# MEMORY.net
KiCad netlist of a schematic drawn in Altium Designer
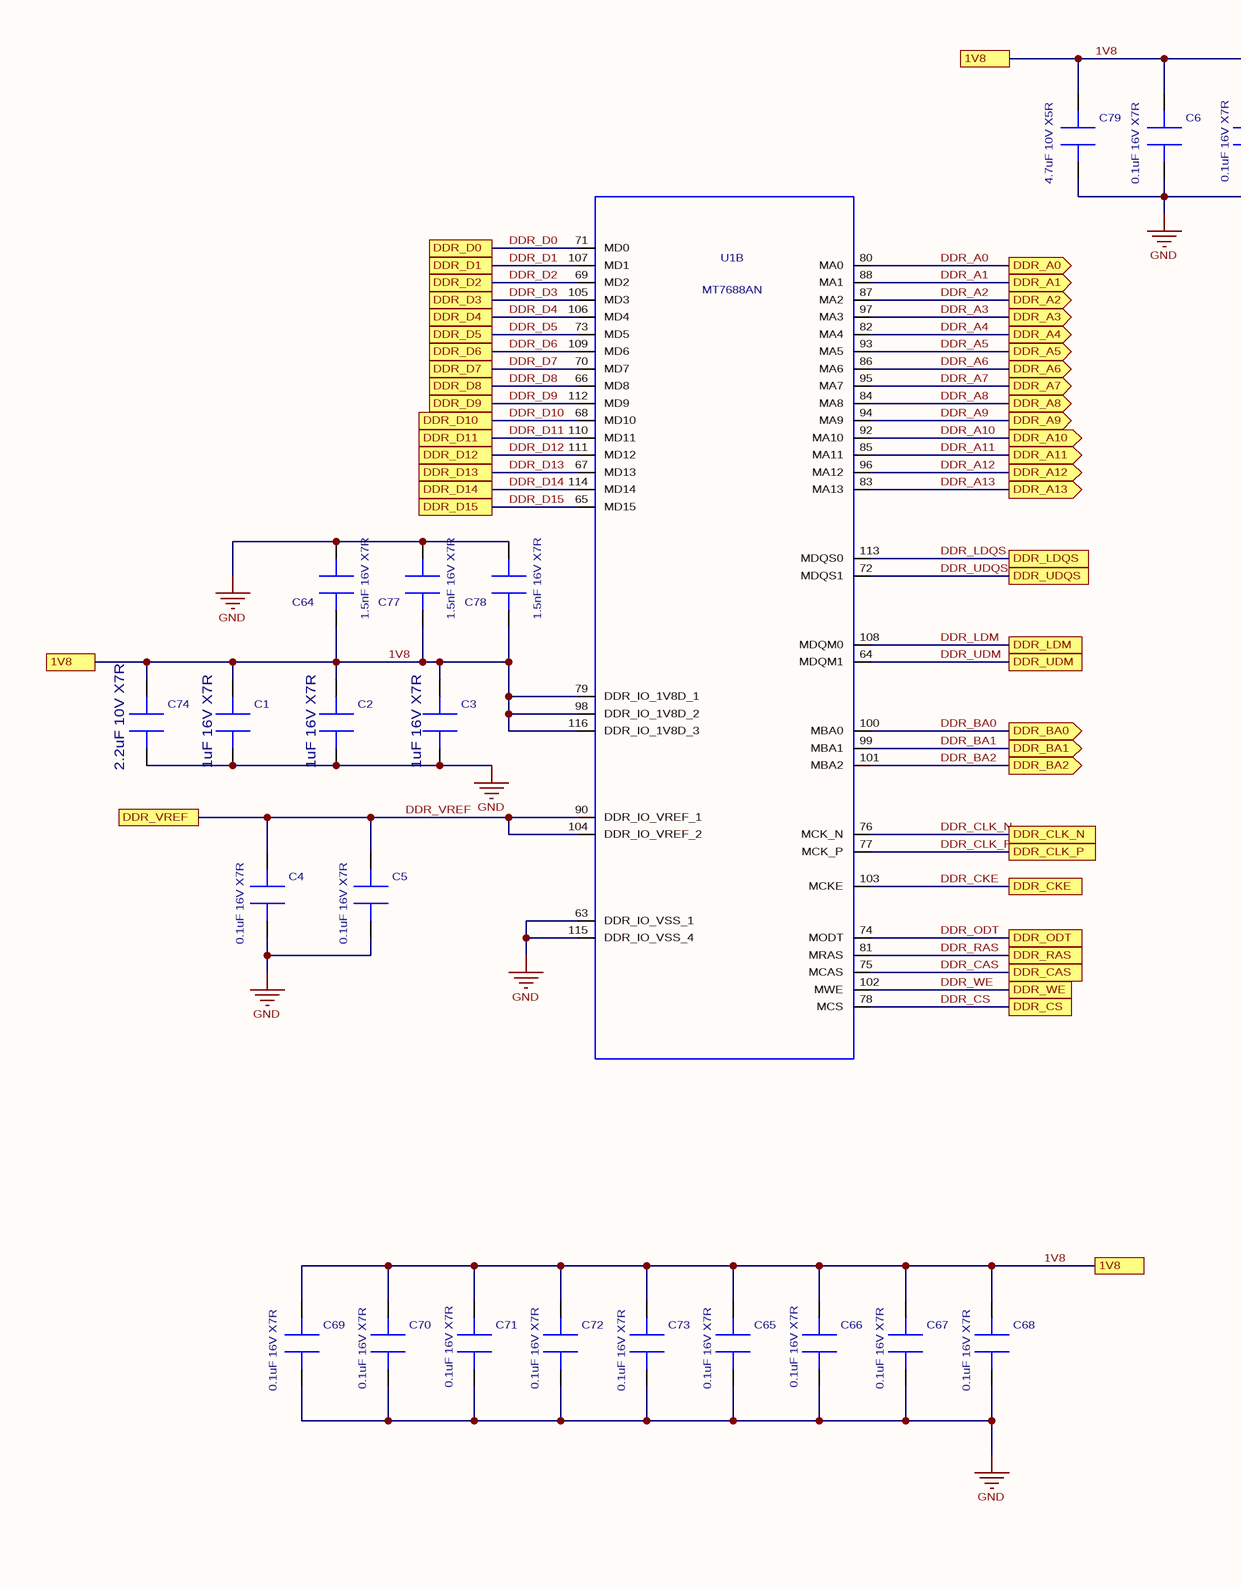
[diagram p0: MEMORY.SchDoc, left]
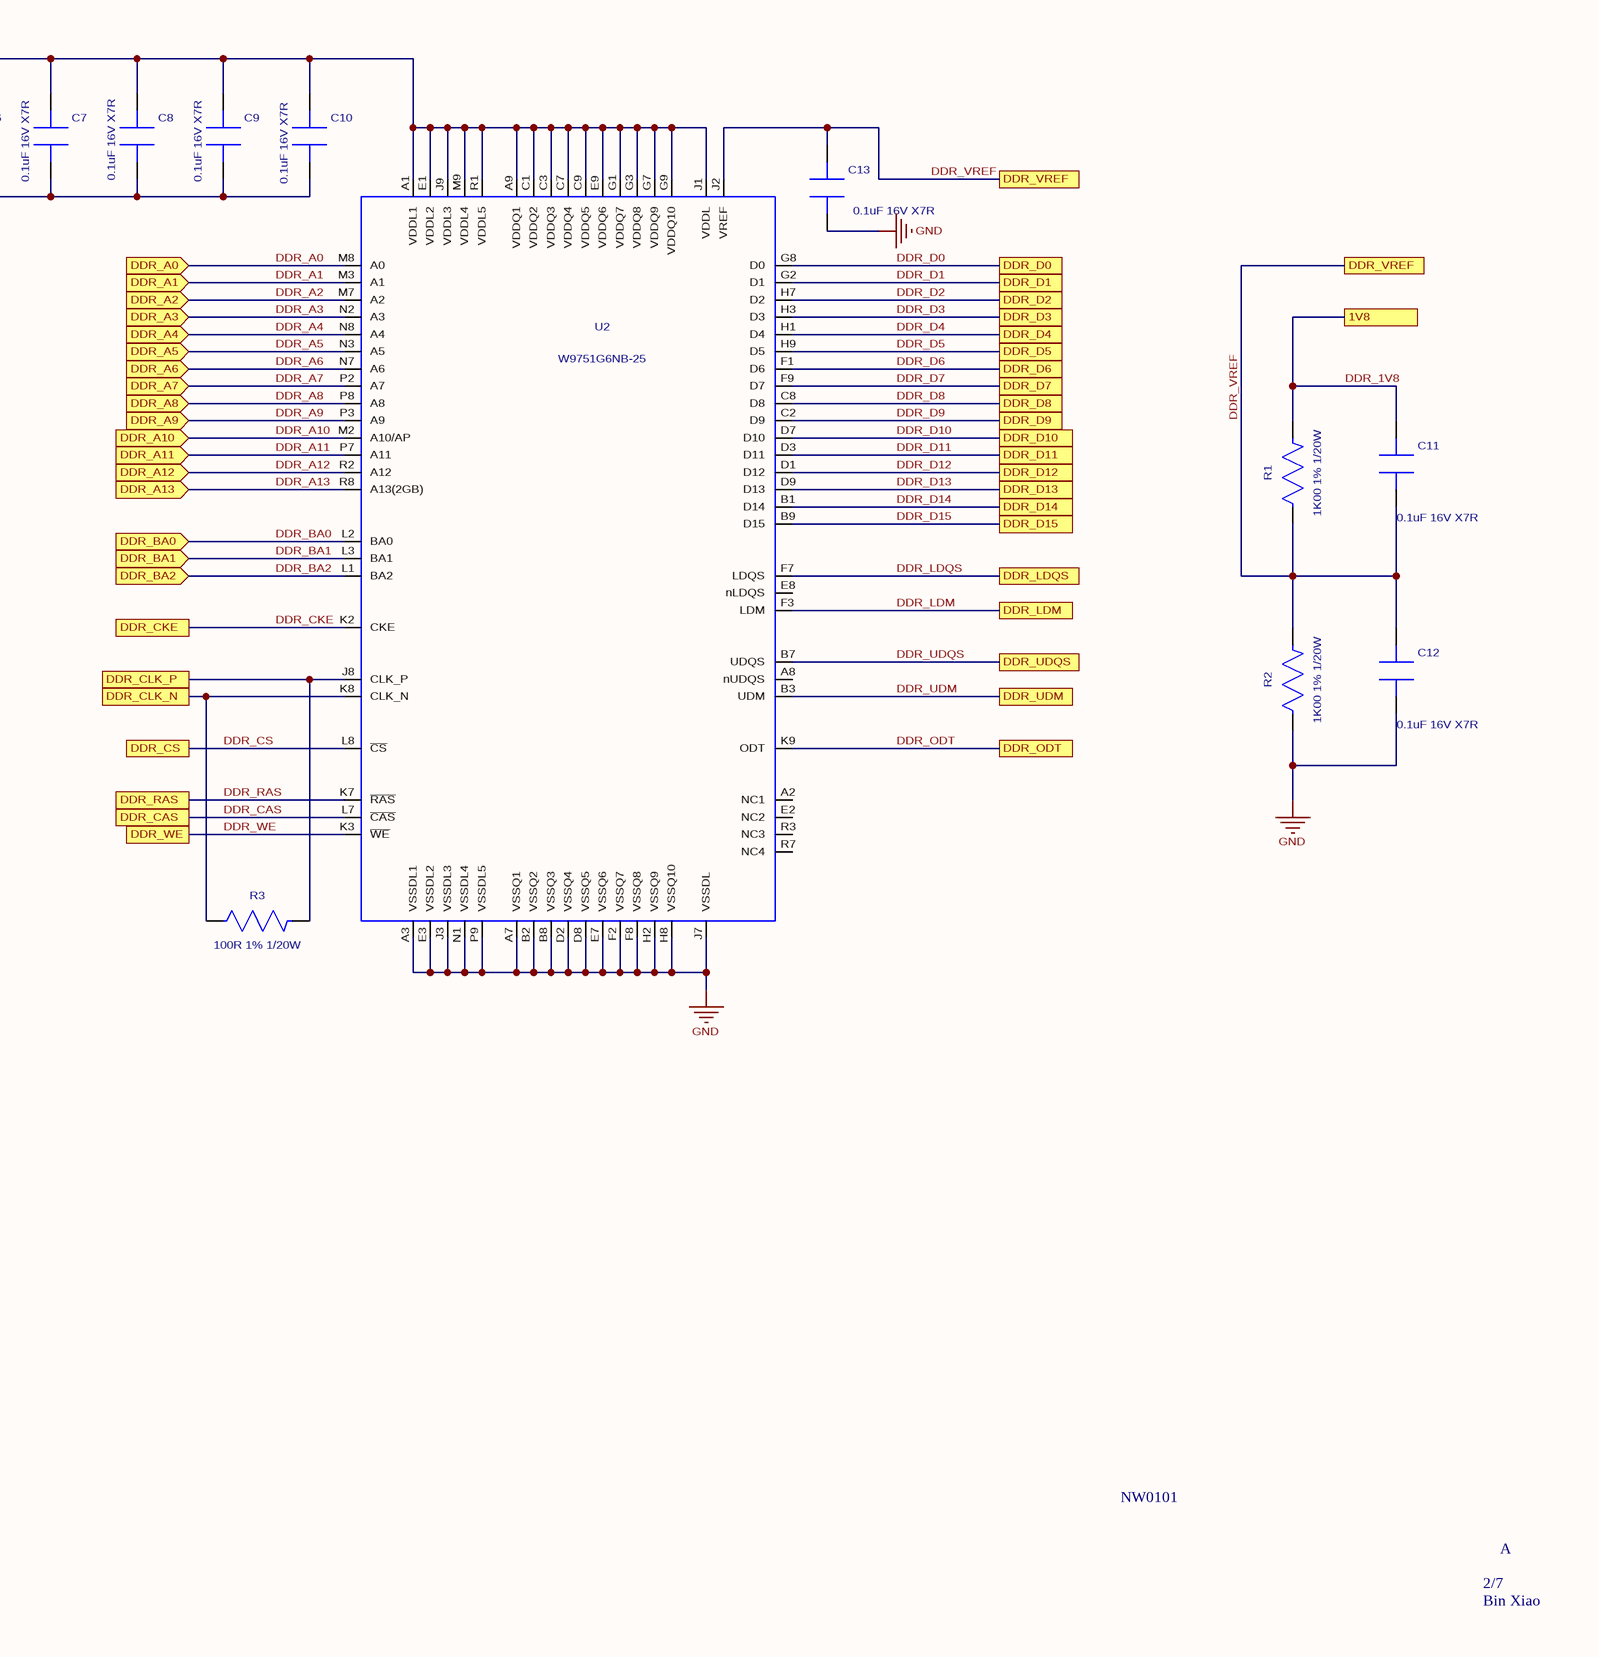
[diagram p1: MEMORY.SchDoc, right]

(export (version "E")
  (design (tool "Eeschema 10.0.6"))
  (components
    (comp (ref "C1")
      (value "1uF 16V X7R")
      (footprint "C0402")
      (description "CAP CER 1UF 6.3V X7R 0402")
      (fields
        (field (name "PART NUMBER") "GRM155R70J105KA12D")
        (field (name "MANUFACTURER") "Murata Electronics")
      )
      (libsource (lib "NetworkModule") (part "CAP0402-105-6.3V-X7R"))
    )
    (comp (ref "C2")
      (value "1uF 16V X7R")
      (footprint "C0402")
      (description "CAP CER 1UF 6.3V X7R 0402")
      (fields
        (field (name "PART NUMBER") "GRM155R70J105KA12D")
        (field (name "MANUFACTURER") "Murata Electronics")
      )
      (libsource (lib "NetworkModule") (part "CAP0402-105-6.3V-X7R"))
    )
    (comp (ref "C3")
      (value "1uF 16V X7R")
      (footprint "C0402")
      (description "CAP CER 1UF 6.3V X7R 0402")
      (fields
        (field (name "PART NUMBER") "GRM155R70J105KA12D")
        (field (name "MANUFACTURER") "Murata Electronics")
      )
      (libsource (lib "NetworkModule") (part "CAP0402-105-6.3V-X7R"))
    )
    (comp (ref "C4")
      (value "0.1uF 16V X7R")
      (footprint "C0201")
      (description "CAP CER 0.1UF 16V X7R 0201")
      (fields
        (field (name "PART NUMBER") "GRM033Z71C104KE14D")
        (field (name "MANUFACTURER") "Murata Electronics")
      )
      (libsource (lib "NetworkModule") (part "CAP0201-104-16V-X7R"))
    )
    (comp (ref "C5")
      (value "0.1uF 16V X7R")
      (footprint "C0201")
      (description "CAP CER 0.1UF 16V X7R 0201")
      (fields
        (field (name "PART NUMBER") "GRM033Z71C104KE14D")
        (field (name "MANUFACTURER") "Murata Electronics")
      )
      (libsource (lib "NetworkModule") (part "CAP0201-104-16V-X7R"))
    )
    (comp (ref "C6")
      (value "0.1uF 16V X7R")
      (footprint "C0201")
      (description "CAP CER 0.1UF 16V X7R 0201")
      (fields
        (field (name "PART NUMBER") "GRM033Z71C104KE14D")
        (field (name "MANUFACTURER") "Murata Electronics")
      )
      (libsource (lib "NetworkModule") (part "CAP0201-104-16V-X7R"))
    )
    (comp (ref "C7")
      (value "0.1uF 16V X7R")
      (footprint "C0201")
      (description "CAP CER 0.1UF 16V X7R 0201")
      (fields
        (field (name "PART NUMBER") "GRM033Z71C104KE14D")
        (field (name "MANUFACTURER") "Murata Electronics")
      )
      (libsource (lib "NetworkModule") (part "CAP0201-104-16V-X7R"))
    )
    (comp (ref "C8")
      (value "0.1uF 16V X7R")
      (footprint "C0201")
      (description "CAP CER 0.1UF 16V X7R 0201")
      (fields
        (field (name "PART NUMBER") "GRM033Z71C104KE14D")
        (field (name "MANUFACTURER") "Murata Electronics")
      )
      (libsource (lib "NetworkModule") (part "CAP0201-104-16V-X7R"))
    )
    (comp (ref "C9")
      (value "0.1uF 16V X7R")
      (footprint "C0201")
      (description "CAP CER 0.1UF 16V X7R 0201")
      (fields
        (field (name "PART NUMBER") "GRM033Z71C104KE14D")
        (field (name "MANUFACTURER") "Murata Electronics")
      )
      (libsource (lib "NetworkModule") (part "CAP0201-104-16V-X7R"))
    )
    (comp (ref "C10")
      (value "0.1uF 16V X7R")
      (footprint "C0201")
      (description "CAP CER 0.1UF 16V X7R 0201")
      (fields
        (field (name "PART NUMBER") "GRM033Z71C104KE14D")
        (field (name "MANUFACTURER") "Murata Electronics")
      )
      (libsource (lib "NetworkModule") (part "CAP0201-104-16V-X7R"))
    )
    (comp (ref "C11")
      (value "0.1uF 16V X7R")
      (footprint "C0201")
      (description "CAP CER 0.1UF 16V X7R 0201")
      (fields
        (field (name "PART NUMBER") "GRM033Z71C104KE14D")
        (field (name "MANUFACTURER") "Murata Electronics")
      )
      (libsource (lib "NetworkModule") (part "CAP0201-104-16V-X7R"))
    )
    (comp (ref "C12")
      (value "0.1uF 16V X7R")
      (footprint "C0201")
      (description "CAP CER 0.1UF 16V X7R 0201")
      (fields
        (field (name "PART NUMBER") "GRM033Z71C104KE14D")
        (field (name "MANUFACTURER") "Murata Electronics")
      )
      (libsource (lib "NetworkModule") (part "CAP0201-104-16V-X7R"))
    )
    (comp (ref "C13")
      (value "0.1uF 16V X7R")
      (footprint "C0201")
      (description "CAP CER 0.1UF 16V X7R 0201")
      (fields
        (field (name "PART NUMBER") "GRM033Z71C104KE14D")
        (field (name "MANUFACTURER") "Murata Electronics")
      )
      (libsource (lib "NetworkModule") (part "CAP0201-104-16V-X7R"))
    )
    (comp (ref "C64")
      (value "1.5nF 16V X7R")
      (footprint "C0201")
      (description "CAP CER 1500PF 16V X7R 0201")
      (fields
        (field (name "PART NUMBER") "CGA1A2X7R1C152K030BA")
        (field (name "MANUFACTURER") "TDK Corporation")
      )
      (libsource (lib "NetworkModule") (part "CAP0201-152-16V-X7R"))
    )
    (comp (ref "C65")
      (value "0.1uF 16V X7R")
      (footprint "C0201")
      (description "CAP CER 0.1UF 16V X7R 0201")
      (fields
        (field (name "PART NUMBER") "GRM033Z71C104KE14D")
        (field (name "MANUFACTURER") "Murata Electronics")
      )
      (libsource (lib "NetworkModule") (part "CAP0201-104-16V-X7R"))
    )
    (comp (ref "C66")
      (value "0.1uF 16V X7R")
      (footprint "C0201")
      (description "CAP CER 0.1UF 16V X7R 0201")
      (fields
        (field (name "PART NUMBER") "GRM033Z71C104KE14D")
        (field (name "MANUFACTURER") "Murata Electronics")
      )
      (libsource (lib "NetworkModule") (part "CAP0201-104-16V-X7R"))
    )
    (comp (ref "C67")
      (value "0.1uF 16V X7R")
      (footprint "C0201")
      (description "CAP CER 0.1UF 16V X7R 0201")
      (fields
        (field (name "PART NUMBER") "GRM033Z71C104KE14D")
        (field (name "MANUFACTURER") "Murata Electronics")
      )
      (libsource (lib "NetworkModule") (part "CAP0201-104-16V-X7R"))
    )
    (comp (ref "C68")
      (value "0.1uF 16V X7R")
      (footprint "C0201")
      (description "CAP CER 0.1UF 16V X7R 0201")
      (fields
        (field (name "PART NUMBER") "GRM033Z71C104KE14D")
        (field (name "MANUFACTURER") "Murata Electronics")
      )
      (libsource (lib "NetworkModule") (part "CAP0201-104-16V-X7R"))
    )
    (comp (ref "C69")
      (value "0.1uF 16V X7R")
      (footprint "C0201")
      (description "CAP CER 0.1UF 16V X7R 0201")
      (fields
        (field (name "PART NUMBER") "GRM033Z71C104KE14D")
        (field (name "MANUFACTURER") "Murata Electronics")
      )
      (libsource (lib "NetworkModule") (part "CAP0201-104-16V-X7R"))
    )
    (comp (ref "C70")
      (value "0.1uF 16V X7R")
      (footprint "C0201")
      (description "CAP CER 0.1UF 16V X7R 0201")
      (fields
        (field (name "PART NUMBER") "GRM033Z71C104KE14D")
        (field (name "MANUFACTURER") "Murata Electronics")
      )
      (libsource (lib "NetworkModule") (part "CAP0201-104-16V-X7R"))
    )
    (comp (ref "C71")
      (value "0.1uF 16V X7R")
      (footprint "C0201")
      (description "CAP CER 0.1UF 16V X7R 0201")
      (fields
        (field (name "PART NUMBER") "GRM033Z71C104KE14D")
        (field (name "MANUFACTURER") "Murata Electronics")
      )
      (libsource (lib "NetworkModule") (part "CAP0201-104-16V-X7R"))
    )
    (comp (ref "C72")
      (value "0.1uF 16V X7R")
      (footprint "C0201")
      (description "CAP CER 0.1UF 16V X7R 0201")
      (fields
        (field (name "PART NUMBER") "GRM033Z71C104KE14D")
        (field (name "MANUFACTURER") "Murata Electronics")
      )
      (libsource (lib "NetworkModule") (part "CAP0201-104-16V-X7R"))
    )
    (comp (ref "C73")
      (value "0.1uF 16V X7R")
      (footprint "C0201")
      (description "CAP CER 0.1UF 16V X7R 0201")
      (fields
        (field (name "PART NUMBER") "GRM033Z71C104KE14D")
        (field (name "MANUFACTURER") "Murata Electronics")
      )
      (libsource (lib "NetworkModule") (part "CAP0201-104-16V-X7R"))
    )
    (comp (ref "C74")
      (value "2.2uF 10V X7R")
      (footprint "C0402")
      (description "CAP CER 2.2UF 10V X7R 0402")
      (fields
        (field (name "PART NUMBER") "GRM155Z71A225KE01D")
        (field (name "MANUFACTURER") "Murata Electronics")
      )
      (libsource (lib "NetworkModule") (part "CAP0402-225-6.3V-X7R"))
    )
    (comp (ref "C77")
      (value "1.5nF 16V X7R")
      (footprint "C0201")
      (description "CAP CER 1500PF 16V X7R 0201")
      (fields
        (field (name "PART NUMBER") "CGA1A2X7R1C152K030BA")
        (field (name "MANUFACTURER") "TDK Corporation")
      )
      (libsource (lib "NetworkModule") (part "CAP0201-152-16V-X7R"))
    )
    (comp (ref "C78")
      (value "1.5nF 16V X7R")
      (footprint "C0201")
      (description "CAP CER 1500PF 16V X7R 0201")
      (fields
        (field (name "PART NUMBER") "CGA1A2X7R1C152K030BA")
        (field (name "MANUFACTURER") "TDK Corporation")
      )
      (libsource (lib "NetworkModule") (part "CAP0201-152-16V-X7R"))
    )
    (comp (ref "C79")
      (value "4.7uF 10V X5R")
      (footprint "C0402")
      (description "CAP CER 4.7UF 10V X5R 0402")
      (fields
        (field (name "PART NUMBER") "CL05A475MP5NRNC")
        (field (name "MANUFACTURER") "Samsung Electro-Mechanics")
      )
      (libsource (lib "NetworkModule") (part "CAP0402-475-10V-X5R"))
    )
    (comp (ref "R1")
      (value "1K00 1% 1/20W")
      (footprint "R0201")
      (description "RES 1K OHM 1% 1/20W 0201")
      (fields
        (field (name "PART NUMBER") "RMCF0201FT1K00")
        (field (name "MANUFACTURER") "Stackpole Electronics Inc")
      )
      (libsource (lib "NetworkModule") (part "RES0201-1K00"))
    )
    (comp (ref "R2")
      (value "1K00 1% 1/20W")
      (footprint "R0201")
      (description "RES 1K OHM 1% 1/20W 0201")
      (fields
        (field (name "PART NUMBER") "RMCF0201FT1K00")
        (field (name "MANUFACTURER") "Stackpole Electronics Inc")
      )
      (libsource (lib "NetworkModule") (part "RES0201-1K00"))
    )
    (comp (ref "R3")
      (value "100R 1% 1/20W")
      (footprint "R0201")
      (description "RES 100 OHM 1% 1/20W 0201")
      (fields (field (name "MANUFACTURER") "Yageo") (field (name "PART NUMBER") "RC0201FR-07100RL"))
      (libsource (lib "NetworkModule") (part "RES0201-100R"))
    )
    (comp (ref "U1")
      (value "MT7688AN")
      (footprint "DR-QFN-128")
      (description "580Mhz 32bits Networking Processor")
      (fields (field (name "MANUFACTURER") "MediaTek Inc"))
      (libsource (lib "*") (part "MT7688AN"))
    )
    (comp (ref "U2")
      (value "W9751G6NB-25")
      (footprint "TWBGA-84_8X12P5_ISI")
      (description "IC DRAM 512MBIT PARALLEL 84VFBGA")
      (fields (field (name "MANUFACTURER") "Winbond Electronics"))
      (libsource (lib "NetworkModule") (part "W9751G6NB-25"))
    )
  )
  (nets
    (net (code "1") (name "/1V8") (class "Default")
      (node (ref "C1") (pin "1") (pinfunction "1_1") (pintype "passive"))
      (node (ref "C10") (pin "1") (pinfunction "1_1") (pintype "passive"))
      (node (ref "C11") (pin "1") (pinfunction "1_1") (pintype "passive"))
      (node (ref "C2") (pin "1") (pinfunction "1_1") (pintype "passive"))
      (node (ref "C3") (pin "1") (pinfunction "1_1") (pintype "passive"))
      (node (ref "C6") (pin "1") (pinfunction "1_1") (pintype "passive"))
      (node (ref "C64") (pin "1") (pinfunction "1_1") (pintype "passive"))
      (node (ref "C65") (pin "1") (pinfunction "1_1") (pintype "passive"))
      (node (ref "C66") (pin "1") (pinfunction "1_1") (pintype "passive"))
      (node (ref "C67") (pin "1") (pinfunction "1_1") (pintype "passive"))
      (node (ref "C68") (pin "1") (pinfunction "1_1") (pintype "passive"))
      (node (ref "C69") (pin "1") (pinfunction "1_1") (pintype "passive"))
      (node (ref "C7") (pin "1") (pinfunction "1_1") (pintype "passive"))
      (node (ref "C70") (pin "1") (pinfunction "1_1") (pintype "passive"))
      (node (ref "C71") (pin "1") (pinfunction "1_1") (pintype "passive"))
      (node (ref "C72") (pin "1") (pinfunction "1_1") (pintype "passive"))
      (node (ref "C73") (pin "1") (pinfunction "1_1") (pintype "passive"))
      (node (ref "C74") (pin "1") (pinfunction "1_1") (pintype "passive"))
      (node (ref "C77") (pin "1") (pinfunction "1_1") (pintype "passive"))
      (node (ref "C78") (pin "1") (pinfunction "1_1") (pintype "passive"))
      (node (ref "C79") (pin "1") (pinfunction "1_1") (pintype "passive"))
      (node (ref "C8") (pin "1") (pinfunction "1_1") (pintype "passive"))
      (node (ref "C9") (pin "1") (pinfunction "1_1") (pintype "passive"))
      (node (ref "R1") (pin "2") (pinfunction "2_2") (pintype "passive"))
      (node (ref "U1") (pin "116") (pinfunction "DDR_IO_1V8D_3_116") (pintype "passive"))
      (node (ref "U1") (pin "79") (pinfunction "DDR_IO_1V8D_1_79") (pintype "passive"))
      (node (ref "U1") (pin "98") (pinfunction "DDR_IO_1V8D_2_98") (pintype "passive"))
      (node (ref "U2") (pin "A1") (pinfunction "VDDL1_A1") (pintype "passive"))
      (node (ref "U2") (pin "A9") (pinfunction "VDDQ1_A9") (pintype "passive"))
      (node (ref "U2") (pin "C1") (pinfunction "VDDQ2_C1") (pintype "passive"))
      (node (ref "U2") (pin "C3") (pinfunction "VDDQ3_C3") (pintype "passive"))
      (node (ref "U2") (pin "C7") (pinfunction "VDDQ4_C7") (pintype "passive"))
      (node (ref "U2") (pin "C9") (pinfunction "VDDQ5_C9") (pintype "passive"))
      (node (ref "U2") (pin "E1") (pinfunction "VDDL2_E1") (pintype "passive"))
      (node (ref "U2") (pin "E9") (pinfunction "VDDQ6_E9") (pintype "passive"))
      (node (ref "U2") (pin "G1") (pinfunction "VDDQ7_G1") (pintype "passive"))
      (node (ref "U2") (pin "G3") (pinfunction "VDDQ8_G3") (pintype "passive"))
      (node (ref "U2") (pin "G7") (pinfunction "VDDQ9_G7") (pintype "passive"))
      (node (ref "U2") (pin "G9") (pinfunction "VDDQ10_G9") (pintype "passive"))
      (node (ref "U2") (pin "J1") (pinfunction "VDDL_J1") (pintype "passive"))
      (node (ref "U2") (pin "J9") (pinfunction "VDDL3_J9") (pintype "passive"))
      (node (ref "U2") (pin "M9") (pinfunction "VDDL4_M9") (pintype "passive"))
      (node (ref "U2") (pin "R1") (pinfunction "VDDL5_R1") (pintype "passive"))
    )
    (net (code "2") (name "/DDR_A0") (class "Default")
      (node (ref "U1") (pin "80") (pinfunction "MA0_80") (pintype "passive"))
      (node (ref "U2") (pin "M8") (pinfunction "A0_M8") (pintype "passive"))
    )
    (net (code "3") (name "/DDR_A1") (class "Default")
      (node (ref "U1") (pin "88") (pinfunction "MA1_88") (pintype "passive"))
      (node (ref "U2") (pin "M3") (pinfunction "A1_M3") (pintype "passive"))
    )
    (net (code "4") (name "/DDR_A2") (class "Default")
      (node (ref "U1") (pin "87") (pinfunction "MA2_87") (pintype "passive"))
      (node (ref "U2") (pin "M7") (pinfunction "A2_M7") (pintype "passive"))
    )
    (net (code "5") (name "/DDR_A3") (class "Default")
      (node (ref "U1") (pin "97") (pinfunction "MA3_97") (pintype "passive"))
      (node (ref "U2") (pin "N2") (pinfunction "A3_N2") (pintype "passive"))
    )
    (net (code "6") (name "/DDR_A4") (class "Default")
      (node (ref "U1") (pin "82") (pinfunction "MA4_82") (pintype "passive"))
      (node (ref "U2") (pin "N8") (pinfunction "A4_N8") (pintype "passive"))
    )
    (net (code "7") (name "/DDR_A5") (class "Default")
      (node (ref "U1") (pin "93") (pinfunction "MA5_93") (pintype "passive"))
      (node (ref "U2") (pin "N3") (pinfunction "A5_N3") (pintype "passive"))
    )
    (net (code "8") (name "/DDR_A6") (class "Default")
      (node (ref "U1") (pin "86") (pinfunction "MA6_86") (pintype "passive"))
      (node (ref "U2") (pin "N7") (pinfunction "A6_N7") (pintype "passive"))
    )
    (net (code "9") (name "/DDR_A7") (class "Default")
      (node (ref "U1") (pin "95") (pinfunction "MA7_95") (pintype "passive"))
      (node (ref "U2") (pin "P2") (pinfunction "A7_P2") (pintype "passive"))
    )
    (net (code "10") (name "/DDR_A8") (class "Default")
      (node (ref "U1") (pin "84") (pinfunction "MA8_84") (pintype "passive"))
      (node (ref "U2") (pin "P8") (pinfunction "A8_P8") (pintype "passive"))
    )
    (net (code "11") (name "/DDR_A9") (class "Default")
      (node (ref "U1") (pin "94") (pinfunction "MA9_94") (pintype "passive"))
      (node (ref "U2") (pin "P3") (pinfunction "A9_P3") (pintype "passive"))
    )
    (net (code "12") (name "/DDR_A10") (class "Default")
      (node (ref "U1") (pin "92") (pinfunction "MA10_92") (pintype "passive"))
      (node (ref "U2") (pin "M2") (pinfunction "A10/AP_M2") (pintype "passive"))
    )
    (net (code "13") (name "/DDR_A11") (class "Default")
      (node (ref "U1") (pin "85") (pinfunction "MA11_85") (pintype "passive"))
      (node (ref "U2") (pin "P7") (pinfunction "A11_P7") (pintype "passive"))
    )
    (net (code "14") (name "/DDR_A12") (class "Default")
      (node (ref "U1") (pin "96") (pinfunction "MA12_96") (pintype "passive"))
      (node (ref "U2") (pin "R2") (pinfunction "A12_R2") (pintype "passive"))
    )
    (net (code "15") (name "/DDR_A13") (class "Default")
      (node (ref "U1") (pin "83") (pinfunction "MA13_83") (pintype "passive"))
      (node (ref "U2") (pin "R8") (pinfunction "A13(2GB)_R8") (pintype "passive"))
    )
    (net (code "16") (name "/DDR_BA0") (class "Default")
      (node (ref "U1") (pin "100") (pinfunction "MBA0_100") (pintype "passive"))
      (node (ref "U2") (pin "L2") (pinfunction "BA0_L2") (pintype "passive"))
    )
    (net (code "17") (name "/DDR_BA1") (class "Default")
      (node (ref "U1") (pin "99") (pinfunction "MBA1_99") (pintype "passive"))
      (node (ref "U2") (pin "L3") (pinfunction "BA1_L3") (pintype "passive"))
    )
    (net (code "18") (name "/DDR_BA2") (class "Default")
      (node (ref "U1") (pin "101") (pinfunction "MBA2_101") (pintype "passive"))
      (node (ref "U2") (pin "L1") (pinfunction "BA2_L1") (pintype "passive"))
    )
    (net (code "19") (name "/DDR_CAS") (class "Default")
      (node (ref "U1") (pin "75") (pinfunction "MCAS_75") (pintype "passive"))
      (node (ref "U2") (pin "L7") (pinfunction "CAS_L7") (pintype "passive"))
    )
    (net (code "20") (name "/DDR_CKE") (class "Default")
      (node (ref "U1") (pin "103") (pinfunction "MCKE_103") (pintype "passive"))
      (node (ref "U2") (pin "K2") (pinfunction "CKE_K2") (pintype "passive"))
    )
    (net (code "21") (name "/DDR_CLK_N") (class "Default")
      (node (ref "R3") (pin "1") (pinfunction "1_1") (pintype "passive"))
      (node (ref "U1") (pin "76") (pinfunction "MCK_N_76") (pintype "passive"))
      (node (ref "U2") (pin "K8") (pinfunction "CLK_N_K8") (pintype "passive"))
    )
    (net (code "22") (name "/DDR_CLK_P") (class "Default")
      (node (ref "R3") (pin "2") (pinfunction "2_2") (pintype "passive"))
      (node (ref "U1") (pin "77") (pinfunction "MCK_P_77") (pintype "passive"))
      (node (ref "U2") (pin "J8") (pinfunction "CLK_P_J8") (pintype "passive"))
    )
    (net (code "23") (name "/DDR_CS") (class "Default")
      (node (ref "U1") (pin "78") (pinfunction "MCS_78") (pintype "passive"))
      (node (ref "U2") (pin "L8") (pinfunction "CS_L8") (pintype "passive"))
    )
    (net (code "24") (name "/DDR_D0") (class "Default")
      (node (ref "U1") (pin "71") (pinfunction "MD0_71") (pintype "passive"))
      (node (ref "U2") (pin "G8") (pinfunction "D0_G8") (pintype "passive"))
    )
    (net (code "25") (name "/DDR_D1") (class "Default")
      (node (ref "U1") (pin "107") (pinfunction "MD1_107") (pintype "passive"))
      (node (ref "U2") (pin "G2") (pinfunction "D1_G2") (pintype "passive"))
    )
    (net (code "26") (name "/DDR_D2") (class "Default")
      (node (ref "U1") (pin "69") (pinfunction "MD2_69") (pintype "passive"))
      (node (ref "U2") (pin "H7") (pinfunction "D2_H7") (pintype "passive"))
    )
    (net (code "27") (name "/DDR_D3") (class "Default")
      (node (ref "U1") (pin "105") (pinfunction "MD3_105") (pintype "passive"))
      (node (ref "U2") (pin "H3") (pinfunction "D3_H3") (pintype "passive"))
    )
    (net (code "28") (name "/DDR_D4") (class "Default")
      (node (ref "U1") (pin "106") (pinfunction "MD4_106") (pintype "passive"))
      (node (ref "U2") (pin "H1") (pinfunction "D4_H1") (pintype "passive"))
    )
    (net (code "29") (name "/DDR_D5") (class "Default")
      (node (ref "U1") (pin "73") (pinfunction "MD5_73") (pintype "passive"))
      (node (ref "U2") (pin "H9") (pinfunction "D5_H9") (pintype "passive"))
    )
    (net (code "30") (name "/DDR_D6") (class "Default")
      (node (ref "U1") (pin "109") (pinfunction "MD6_109") (pintype "passive"))
      (node (ref "U2") (pin "F1") (pinfunction "D6_F1") (pintype "passive"))
    )
    (net (code "31") (name "/DDR_D7") (class "Default")
      (node (ref "U1") (pin "70") (pinfunction "MD7_70") (pintype "passive"))
      (node (ref "U2") (pin "F9") (pinfunction "D7_F9") (pintype "passive"))
    )
    (net (code "32") (name "/DDR_D8") (class "Default")
      (node (ref "U1") (pin "66") (pinfunction "MD8_66") (pintype "passive"))
      (node (ref "U2") (pin "C8") (pinfunction "D8_C8") (pintype "passive"))
    )
    (net (code "33") (name "/DDR_D9") (class "Default")
      (node (ref "U1") (pin "112") (pinfunction "MD9_112") (pintype "passive"))
      (node (ref "U2") (pin "C2") (pinfunction "D9_C2") (pintype "passive"))
    )
    (net (code "34") (name "/DDR_D10") (class "Default")
      (node (ref "U1") (pin "68") (pinfunction "MD10_68") (pintype "passive"))
      (node (ref "U2") (pin "D7") (pinfunction "D10_D7") (pintype "passive"))
    )
    (net (code "35") (name "/DDR_D11") (class "Default")
      (node (ref "U1") (pin "110") (pinfunction "MD11_110") (pintype "passive"))
      (node (ref "U2") (pin "D3") (pinfunction "D11_D3") (pintype "passive"))
    )
    (net (code "36") (name "/DDR_D12") (class "Default")
      (node (ref "U1") (pin "111") (pinfunction "MD12_111") (pintype "passive"))
      (node (ref "U2") (pin "D1") (pinfunction "D12_D1") (pintype "passive"))
    )
    (net (code "37") (name "/DDR_D13") (class "Default")
      (node (ref "U1") (pin "67") (pinfunction "MD13_67") (pintype "passive"))
      (node (ref "U2") (pin "D9") (pinfunction "D13_D9") (pintype "passive"))
    )
    (net (code "38") (name "/DDR_D14") (class "Default")
      (node (ref "U1") (pin "114") (pinfunction "MD14_114") (pintype "passive"))
      (node (ref "U2") (pin "B1") (pinfunction "D14_B1") (pintype "passive"))
    )
    (net (code "39") (name "/DDR_D15") (class "Default")
      (node (ref "U1") (pin "65") (pinfunction "MD15_65") (pintype "passive"))
      (node (ref "U2") (pin "B9") (pinfunction "D15_B9") (pintype "passive"))
    )
    (net (code "40") (name "/DDR_LDM") (class "Default")
      (node (ref "U1") (pin "108") (pinfunction "MDQM0_108") (pintype "passive"))
      (node (ref "U2") (pin "F3") (pinfunction "LDM_F3") (pintype "passive"))
    )
    (net (code "41") (name "/DDR_LDQS") (class "Default")
      (node (ref "U1") (pin "113") (pinfunction "MDQS0_113") (pintype "passive"))
      (node (ref "U2") (pin "F7") (pinfunction "LDQS_F7") (pintype "passive"))
    )
    (net (code "42") (name "/DDR_ODT") (class "Default")
      (node (ref "U1") (pin "74") (pinfunction "MODT_74") (pintype "passive"))
      (node (ref "U2") (pin "K9") (pinfunction "ODT_K9") (pintype "passive"))
    )
    (net (code "43") (name "/DDR_RAS") (class "Default")
      (node (ref "U1") (pin "81") (pinfunction "MRAS_81") (pintype "passive"))
      (node (ref "U2") (pin "K7") (pinfunction "RAS_K7") (pintype "passive"))
    )
    (net (code "44") (name "/DDR_UDM") (class "Default")
      (node (ref "U1") (pin "64") (pinfunction "MDQM1_64") (pintype "passive"))
      (node (ref "U2") (pin "B3") (pinfunction "UDM_B3") (pintype "passive"))
    )
    (net (code "45") (name "/DDR_UDQS") (class "Default")
      (node (ref "U1") (pin "72") (pinfunction "MDQS1_72") (pintype "passive"))
      (node (ref "U2") (pin "B7") (pinfunction "UDQS_B7") (pintype "passive"))
    )
    (net (code "46") (name "/DDR_VREF") (class "Default")
      (node (ref "C11") (pin "2") (pinfunction "2_2") (pintype "passive"))
      (node (ref "C12") (pin "1") (pinfunction "1_1") (pintype "passive"))
      (node (ref "C13") (pin "1") (pinfunction "1_1") (pintype "passive"))
      (node (ref "C4") (pin "1") (pinfunction "1_1") (pintype "passive"))
      (node (ref "C5") (pin "1") (pinfunction "1_1") (pintype "passive"))
      (node (ref "R1") (pin "1") (pinfunction "1_1") (pintype "passive"))
      (node (ref "R2") (pin "2") (pinfunction "2_2") (pintype "passive"))
      (node (ref "U1") (pin "104") (pinfunction "DDR_IO_VREF_2_104") (pintype "passive"))
      (node (ref "U1") (pin "90") (pinfunction "DDR_IO_VREF_1_90") (pintype "passive"))
      (node (ref "U2") (pin "J2") (pinfunction "VREF_J2") (pintype "passive"))
    )
    (net (code "47") (name "/DDR_WE") (class "Default")
      (node (ref "U1") (pin "102") (pinfunction "MWE_102") (pintype "passive"))
      (node (ref "U2") (pin "K3") (pinfunction "WE_K3") (pintype "passive"))
    )
    (net (code "48") (name "GND") (class "Default")
      (node (ref "C1") (pin "2") (pinfunction "2_2") (pintype "passive"))
      (node (ref "C10") (pin "2") (pinfunction "2_2") (pintype "passive"))
      (node (ref "C12") (pin "2") (pinfunction "2_2") (pintype "passive"))
      (node (ref "C13") (pin "2") (pinfunction "2_2") (pintype "passive"))
      (node (ref "C2") (pin "2") (pinfunction "2_2") (pintype "passive"))
      (node (ref "C3") (pin "2") (pinfunction "2_2") (pintype "passive"))
      (node (ref "C4") (pin "2") (pinfunction "2_2") (pintype "passive"))
      (node (ref "C5") (pin "2") (pinfunction "2_2") (pintype "passive"))
      (node (ref "C6") (pin "2") (pinfunction "2_2") (pintype "passive"))
      (node (ref "C64") (pin "2") (pinfunction "2_2") (pintype "passive"))
      (node (ref "C65") (pin "2") (pinfunction "2_2") (pintype "passive"))
      (node (ref "C66") (pin "2") (pinfunction "2_2") (pintype "passive"))
      (node (ref "C67") (pin "2") (pinfunction "2_2") (pintype "passive"))
      (node (ref "C68") (pin "2") (pinfunction "2_2") (pintype "passive"))
      (node (ref "C69") (pin "2") (pinfunction "2_2") (pintype "passive"))
      (node (ref "C7") (pin "2") (pinfunction "2_2") (pintype "passive"))
      (node (ref "C70") (pin "2") (pinfunction "2_2") (pintype "passive"))
      (node (ref "C71") (pin "2") (pinfunction "2_2") (pintype "passive"))
      (node (ref "C72") (pin "2") (pinfunction "2_2") (pintype "passive"))
      (node (ref "C73") (pin "2") (pinfunction "2_2") (pintype "passive"))
      (node (ref "C74") (pin "2") (pinfunction "2_2") (pintype "passive"))
      (node (ref "C77") (pin "2") (pinfunction "2_2") (pintype "passive"))
      (node (ref "C78") (pin "2") (pinfunction "2_2") (pintype "passive"))
      (node (ref "C79") (pin "2") (pinfunction "2_2") (pintype "passive"))
      (node (ref "C8") (pin "2") (pinfunction "2_2") (pintype "passive"))
      (node (ref "C9") (pin "2") (pinfunction "2_2") (pintype "passive"))
      (node (ref "R2") (pin "1") (pinfunction "1_1") (pintype "passive"))
      (node (ref "U1") (pin "115") (pinfunction "DDR_IO_VSS_4_115") (pintype "passive"))
      (node (ref "U1") (pin "63") (pinfunction "DDR_IO_VSS_1_63") (pintype "passive"))
      (node (ref "U2") (pin "A3") (pinfunction "VSSDL1_A3") (pintype "passive"))
      (node (ref "U2") (pin "A7") (pinfunction "VSSQ1_A7") (pintype "passive"))
      (node (ref "U2") (pin "B2") (pinfunction "VSSQ2_B2") (pintype "passive"))
      (node (ref "U2") (pin "B8") (pinfunction "VSSQ3_B8") (pintype "passive"))
      (node (ref "U2") (pin "D2") (pinfunction "VSSQ4_D2") (pintype "passive"))
      (node (ref "U2") (pin "D8") (pinfunction "VSSQ5_D8") (pintype "passive"))
      (node (ref "U2") (pin "E3") (pinfunction "VSSDL2_E3") (pintype "passive"))
      (node (ref "U2") (pin "E7") (pinfunction "VSSQ6_E7") (pintype "passive"))
      (node (ref "U2") (pin "F2") (pinfunction "VSSQ7_F2") (pintype "passive"))
      (node (ref "U2") (pin "F8") (pinfunction "VSSQ8_F8") (pintype "passive"))
      (node (ref "U2") (pin "H2") (pinfunction "VSSQ9_H2") (pintype "passive"))
      (node (ref "U2") (pin "H8") (pinfunction "VSSQ10_H8") (pintype "passive"))
      (node (ref "U2") (pin "J3") (pinfunction "VSSDL3_J3") (pintype "passive"))
      (node (ref "U2") (pin "J7") (pinfunction "VSSDL_J7") (pintype "passive"))
      (node (ref "U2") (pin "N1") (pinfunction "VSSDL4_N1") (pintype "passive"))
      (node (ref "U2") (pin "P9") (pinfunction "VSSDL5_P9") (pintype "passive"))
    )
    (net (code "49") (name "unconnected-(U2-NC1-PadA2)") (class "Default")
      (node (ref "U2") (pin "A2") (pinfunction "NC1_A2") (pintype "passive"))
    )
    (net (code "50") (name "unconnected-(U2-NC2-PadE2)") (class "Default")
      (node (ref "U2") (pin "E2") (pinfunction "NC2_E2") (pintype "passive"))
    )
    (net (code "51") (name "unconnected-(U2-NC3-PadR3)") (class "Default")
      (node (ref "U2") (pin "R3") (pinfunction "NC3_R3") (pintype "passive"))
    )
    (net (code "52") (name "unconnected-(U2-NC4-PadR7)") (class "Default")
      (node (ref "U2") (pin "R7") (pinfunction "NC4_R7") (pintype "passive"))
    )
    (net (code "53") (name "unconnected-(U2-nLDQS-PadE8)") (class "Default")
      (node (ref "U2") (pin "E8") (pinfunction "nLDQS_E8") (pintype "passive"))
    )
    (net (code "54") (name "unconnected-(U2-nUDQS-PadA8)") (class "Default")
      (node (ref "U2") (pin "A8") (pinfunction "nUDQS_A8") (pintype "passive"))
    )
  )
)
